# LoopAmp.net
KiCad netlist of a schematic drawn in EAGLE
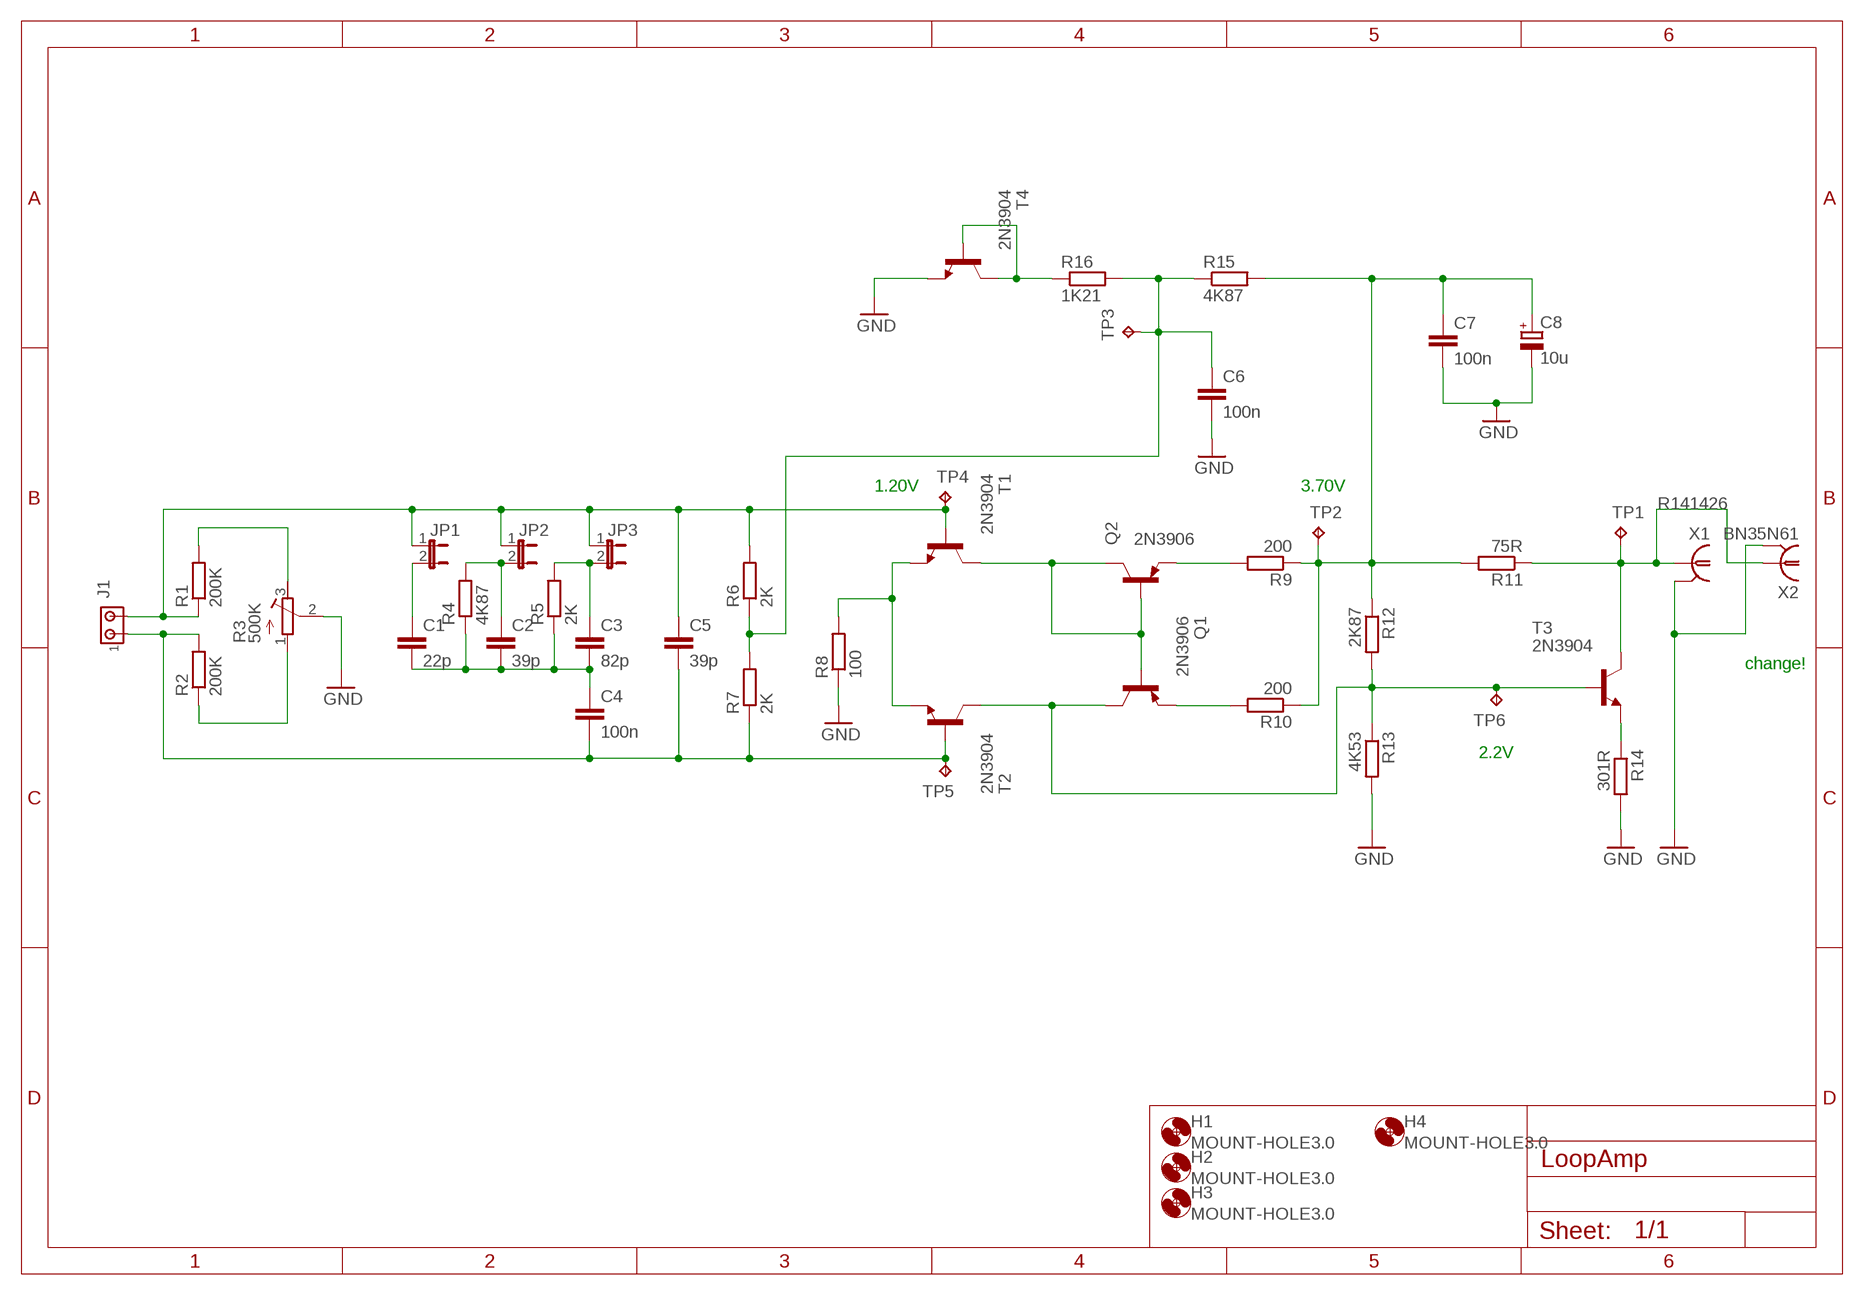
[diagram p0: schematic, sheet 1]

(export (version "E")
  (design (tool "Eeschema 10.0.6"))
  (components
    (comp (ref "C1")
      (value "22p")
      (footprint "eagle-import:C0805")
      (libsource (lib "eagle-import") (part "C-EUC0805"))
    )
    (comp (ref "C2")
      (value "39p")
      (footprint "eagle-import:C0805")
      (libsource (lib "eagle-import") (part "C-EUC0805"))
    )
    (comp (ref "C3")
      (value "82p")
      (footprint "eagle-import:C0805")
      (libsource (lib "eagle-import") (part "C-EUC0805"))
    )
    (comp (ref "C4")
      (value "100n")
      (footprint "eagle-import:C0805")
      (libsource (lib "eagle-import") (part "C-EUC0805"))
    )
    (comp (ref "C5")
      (value "39p")
      (footprint "eagle-import:C0805")
      (libsource (lib "eagle-import") (part "C-EUC0805"))
    )
    (comp (ref "C6")
      (value "100n")
      (footprint "eagle-import:C0805")
      (libsource (lib "eagle-import") (part "C-EUC0805"))
    )
    (comp (ref "C7")
      (value "100n")
      (footprint "eagle-import:C0805")
      (libsource (lib "eagle-import") (part "C-EUC0805"))
    )
    (comp (ref "C8")
      (value "10u")
      (footprint "eagle-import:PANASONIC_C")
      (libsource (lib "eagle-import") (part "CPOL-EUC"))
    )
    (comp (ref "H1")
      (value "MOUNT-HOLE3.0")
      (footprint "eagle-import:3,0")
      (libsource (lib "eagle-import") (part "MOUNT-HOLE3.0"))
    )
    (comp (ref "H2")
      (value "MOUNT-HOLE3.0")
      (footprint "eagle-import:3,0")
      (libsource (lib "eagle-import") (part "MOUNT-HOLE3.0"))
    )
    (comp (ref "H3")
      (value "MOUNT-HOLE3.0")
      (footprint "eagle-import:3,0")
      (libsource (lib "eagle-import") (part "MOUNT-HOLE3.0"))
    )
    (comp (ref "H4")
      (value "MOUNT-HOLE3.0")
      (footprint "eagle-import:3,0")
      (libsource (lib "eagle-import") (part "MOUNT-HOLE3.0"))
    )
    (comp (ref "J1")
      (value "MTA02-156")
      (footprint "eagle-import:1X2MTA")
      (libsource (lib "eagle-import") (part "MTA02-156"))
    )
    (comp (ref "JP1")
      (value "JP1E")
      (footprint "eagle-import:JP1")
      (libsource (lib "eagle-import") (part "JP1E"))
    )
    (comp (ref "JP2")
      (value "JP1E")
      (footprint "eagle-import:JP1")
      (libsource (lib "eagle-import") (part "JP1E"))
    )
    (comp (ref "JP3")
      (value "JP1E")
      (footprint "eagle-import:JP1")
      (libsource (lib "eagle-import") (part "JP1E"))
    )
    (comp (ref "Q1")
      (value "2N3906")
      (footprint "eagle-import:TO92")
      (libsource (lib "eagle-import") (part "2N3906"))
    )
    (comp (ref "Q2")
      (value "2N3906")
      (footprint "eagle-import:TO92")
      (libsource (lib "eagle-import") (part "2N3906"))
    )
    (comp (ref "R1")
      (value "200K")
      (footprint "eagle-import:R0805")
      (libsource (lib "eagle-import") (part "R-EU_R0805"))
    )
    (comp (ref "R2")
      (value "200K")
      (footprint "eagle-import:R0805")
      (libsource (lib "eagle-import") (part "R-EU_R0805"))
    )
    (comp (ref "R3")
      (value "500K")
      (footprint "eagle-import:RTRIM64W")
      (libsource (lib "eagle-import") (part "R-TRIMM64W"))
    )
    (comp (ref "R4")
      (value "4K87")
      (footprint "eagle-import:R0805")
      (libsource (lib "eagle-import") (part "R-EU_R0805"))
    )
    (comp (ref "R5")
      (value "2K")
      (footprint "eagle-import:R0805")
      (libsource (lib "eagle-import") (part "R-EU_R0805"))
    )
    (comp (ref "R6")
      (value "2K")
      (footprint "eagle-import:R0805")
      (libsource (lib "eagle-import") (part "R-EU_R0805"))
    )
    (comp (ref "R7")
      (value "2K")
      (footprint "eagle-import:R0805")
      (libsource (lib "eagle-import") (part "R-EU_R0805"))
    )
    (comp (ref "R8")
      (value "100")
      (footprint "eagle-import:R0805")
      (libsource (lib "eagle-import") (part "R-EU_R0805"))
    )
    (comp (ref "R9")
      (value "200")
      (footprint "eagle-import:R0805")
      (libsource (lib "eagle-import") (part "R-EU_R0805"))
    )
    (comp (ref "R10")
      (value "200")
      (footprint "eagle-import:R0805")
      (libsource (lib "eagle-import") (part "R-EU_R0805"))
    )
    (comp (ref "R11")
      (value "75R")
      (footprint "eagle-import:R0805")
      (libsource (lib "eagle-import") (part "R-EU_R0805"))
    )
    (comp (ref "R12")
      (value "2K87")
      (footprint "eagle-import:R0805")
      (libsource (lib "eagle-import") (part "R-EU_R0805"))
    )
    (comp (ref "R13")
      (value "4K53")
      (footprint "eagle-import:R0805")
      (libsource (lib "eagle-import") (part "R-EU_R0805"))
    )
    (comp (ref "R14")
      (value "301R")
      (footprint "eagle-import:R0805")
      (libsource (lib "eagle-import") (part "R-EU_R0805"))
    )
    (comp (ref "R15")
      (value "4K87")
      (footprint "eagle-import:R0805")
      (libsource (lib "eagle-import") (part "R-EU_R0805"))
    )
    (comp (ref "R16")
      (value "1K21")
      (footprint "eagle-import:R0805")
      (libsource (lib "eagle-import") (part "R-EU_R0805"))
    )
    (comp (ref "T1")
      (value "2N3904")
      (footprint "eagle-import:TO92")
      (libsource (lib "eagle-import") (part "2N3904"))
    )
    (comp (ref "T2")
      (value "2N3904")
      (footprint "eagle-import:TO92")
      (libsource (lib "eagle-import") (part "2N3904"))
    )
    (comp (ref "T3")
      (value "2N3904")
      (footprint "eagle-import:TO92")
      (libsource (lib "eagle-import") (part "2N3904"))
    )
    (comp (ref "T4")
      (value "2N3904")
      (footprint "eagle-import:TO92")
      (libsource (lib "eagle-import") (part "2N3904"))
    )
    (comp (ref "TP1")
      (value "4.18V>")
      (footprint "eagle-import:P1-13")
      (libsource (lib "eagle-import") (part "TPPAD1-13"))
    )
    (comp (ref "TP2")
      (value "4.18V>")
      (footprint "eagle-import:P1-13")
      (libsource (lib "eagle-import") (part "TPPAD1-13"))
    )
    (comp (ref "TP3")
      (value "4.18V>")
      (footprint "eagle-import:P1-13")
      (libsource (lib "eagle-import") (part "TPPAD1-13"))
    )
    (comp (ref "TP4")
      (value "4.18V>")
      (footprint "eagle-import:P1-13")
      (libsource (lib "eagle-import") (part "TPPAD1-13"))
    )
    (comp (ref "TP5")
      (value "4.18V>")
      (footprint "eagle-import:P1-13")
      (libsource (lib "eagle-import") (part "TPPAD1-13"))
    )
    (comp (ref "TP6")
      (value "4.18V>")
      (footprint "eagle-import:P1-13")
      (libsource (lib "eagle-import") (part "TPPAD1-13"))
    )
    (comp (ref "X1")
      (value "R141426")
      (footprint "eagle-import:R141426")
      (fields (field (name "MF") "FARNELL") (field (name "MPN") "R141426161"))
      (libsource (lib "eagle-import") (part "R141426"))
    )
    (comp (ref "X2")
      (value "BN35N61")
      (footprint "eagle-import:B35N61")
      (libsource (lib "eagle-import") (part "BN35N61"))
    )
  )
  (nets
    (net (code "1") (name "GND") (class "Default")
      (node (ref "C6") (pin "2") (pinfunction "2_2") (pintype "passive"))
      (node (ref "C7") (pin "2") (pinfunction "2_2") (pintype "passive"))
      (node (ref "C8") (pin "-") (pinfunction "-_-") (pintype "passive"))
      (node (ref "R13") (pin "2") (pinfunction "2_2") (pintype "passive"))
      (node (ref "R14") (pin "2") (pinfunction "2_2") (pintype "passive"))
      (node (ref "R3") (pin "2") (pinfunction "S_2") (pintype "passive"))
      (node (ref "R8") (pin "1") (pinfunction "1_1") (pintype "passive"))
      (node (ref "T4") (pin "3") (pinfunction "E_3") (pintype "passive"))
      (node (ref "X1") (pin "2") (pinfunction "2_2") (pintype "passive"))
      (node (ref "X1") (pin "3") (pinfunction "2_3") (pintype "passive"))
      (node (ref "X1") (pin "4") (pinfunction "2_4") (pintype "passive"))
      (node (ref "X1") (pin "5") (pinfunction "2_5") (pintype "passive"))
      (node (ref "X2") (pin "2") (pinfunction "2_2") (pintype "passive"))
      (node (ref "X2") (pin "3") (pinfunction "2_3") (pintype "passive"))
      (node (ref "X2") (pin "4") (pinfunction "2_4") (pintype "passive"))
      (node (ref "X2") (pin "5") (pinfunction "2_5") (pintype "passive"))
    )
    (net (code "2") (name "Net-(C1-Pad1)") (class "Default")
      (node (ref "C1") (pin "1") (pinfunction "1_1") (pintype "passive"))
      (node (ref "JP1") (pin "2") (pinfunction "2_2") (pintype "passive"))
    )
    (net (code "3") (name "Net-(C1-Pad2)") (class "Default")
      (node (ref "C1") (pin "2") (pinfunction "2_2") (pintype "passive"))
      (node (ref "C2") (pin "2") (pinfunction "2_2") (pintype "passive"))
      (node (ref "C3") (pin "2") (pinfunction "2_2") (pintype "passive"))
      (node (ref "C4") (pin "1") (pinfunction "1_1") (pintype "passive"))
      (node (ref "R4") (pin "1") (pinfunction "1_1") (pintype "passive"))
      (node (ref "R5") (pin "1") (pinfunction "1_1") (pintype "passive"))
    )
    (net (code "4") (name "Net-(C2-Pad1)") (class "Default")
      (node (ref "C2") (pin "1") (pinfunction "1_1") (pintype "passive"))
      (node (ref "JP2") (pin "2") (pinfunction "2_2") (pintype "passive"))
      (node (ref "R4") (pin "2") (pinfunction "2_2") (pintype "passive"))
    )
    (net (code "5") (name "Net-(C3-Pad1)") (class "Default")
      (node (ref "C3") (pin "1") (pinfunction "1_1") (pintype "passive"))
      (node (ref "JP3") (pin "2") (pinfunction "2_2") (pintype "passive"))
      (node (ref "R5") (pin "2") (pinfunction "2_2") (pintype "passive"))
    )
    (net (code "6") (name "Net-(C6-Pad1)") (class "Default")
      (node (ref "C6") (pin "1") (pinfunction "1_1") (pintype "passive"))
      (node (ref "R15") (pin "1") (pinfunction "1_1") (pintype "passive"))
      (node (ref "R16") (pin "2") (pinfunction "2_2") (pintype "passive"))
      (node (ref "R6") (pin "1") (pinfunction "1_1") (pintype "passive"))
      (node (ref "R7") (pin "2") (pinfunction "2_2") (pintype "passive"))
      (node (ref "TP3") (pin "TP") (pinfunction "TP_TP") (pintype "input"))
    )
    (net (code "7") (name "Net-(C7-Pad1)") (class "Default")
      (node (ref "C7") (pin "1") (pinfunction "1_1") (pintype "passive"))
      (node (ref "C8") (pin "+") (pinfunction "+_+") (pintype "passive"))
      (node (ref "R10") (pin "1") (pinfunction "1_1") (pintype "passive"))
      (node (ref "R11") (pin "2") (pinfunction "2_2") (pintype "passive"))
      (node (ref "R12") (pin "1") (pinfunction "1_1") (pintype "passive"))
      (node (ref "R15") (pin "2") (pinfunction "2_2") (pintype "passive"))
      (node (ref "R9") (pin "1") (pinfunction "1_1") (pintype "passive"))
      (node (ref "TP2") (pin "TP") (pinfunction "TP_TP") (pintype "input"))
    )
    (net (code "8") (name "Net-(Q1-B)") (class "Default")
      (node (ref "Q1") (pin "2") (pinfunction "B_2") (pintype "passive"))
      (node (ref "Q2") (pin "1") (pinfunction "C_1") (pintype "passive"))
      (node (ref "Q2") (pin "2") (pinfunction "B_2") (pintype "passive"))
      (node (ref "T1") (pin "1") (pinfunction "C_1") (pintype "passive"))
    )
    (net (code "9") (name "Net-(Q1-C)") (class "Default")
      (node (ref "Q1") (pin "1") (pinfunction "C_1") (pintype "passive"))
      (node (ref "R12") (pin "2") (pinfunction "2_2") (pintype "passive"))
      (node (ref "R13") (pin "1") (pinfunction "1_1") (pintype "passive"))
      (node (ref "T2") (pin "1") (pinfunction "C_1") (pintype "passive"))
      (node (ref "T3") (pin "2") (pinfunction "B_2") (pintype "passive"))
      (node (ref "TP6") (pin "TP") (pinfunction "TP_TP") (pintype "input"))
    )
    (net (code "10") (name "Net-(Q1-E)") (class "Default")
      (node (ref "Q1") (pin "3") (pinfunction "E_3") (pintype "passive"))
      (node (ref "R10") (pin "2") (pinfunction "2_2") (pintype "passive"))
    )
    (net (code "11") (name "Net-(Q2-E)") (class "Default")
      (node (ref "Q2") (pin "3") (pinfunction "E_3") (pintype "passive"))
      (node (ref "R9") (pin "2") (pinfunction "2_2") (pintype "passive"))
    )
    (net (code "12") (name "Net-(R3-A)") (class "Default")
      (node (ref "R2") (pin "1") (pinfunction "1_1") (pintype "passive"))
      (node (ref "R3") (pin "1") (pinfunction "A_1") (pintype "passive"))
    )
    (net (code "13") (name "Net-(R3-E)") (class "Default")
      (node (ref "R1") (pin "2") (pinfunction "2_2") (pintype "passive"))
      (node (ref "R3") (pin "3") (pinfunction "E_3") (pintype "passive"))
    )
    (net (code "14") (name "Net-(T1-B)") (class "Default")
      (node (ref "C5") (pin "1") (pinfunction "1_1") (pintype "passive"))
      (node (ref "J1") (pin "2") (pinfunction "2_2") (pintype "passive"))
      (node (ref "JP1") (pin "1") (pinfunction "1_1") (pintype "passive"))
      (node (ref "JP2") (pin "1") (pinfunction "1_1") (pintype "passive"))
      (node (ref "JP3") (pin "1") (pinfunction "1_1") (pintype "passive"))
      (node (ref "R1") (pin "1") (pinfunction "1_1") (pintype "passive"))
      (node (ref "R6") (pin "2") (pinfunction "2_2") (pintype "passive"))
      (node (ref "T1") (pin "2") (pinfunction "B_2") (pintype "passive"))
      (node (ref "TP4") (pin "TP") (pinfunction "TP_TP") (pintype "input"))
    )
    (net (code "15") (name "Net-(T1-E)") (class "Default")
      (node (ref "R8") (pin "2") (pinfunction "2_2") (pintype "passive"))
      (node (ref "T1") (pin "3") (pinfunction "E_3") (pintype "passive"))
      (node (ref "T2") (pin "3") (pinfunction "E_3") (pintype "passive"))
    )
    (net (code "16") (name "Net-(T2-B)") (class "Default")
      (node (ref "C4") (pin "2") (pinfunction "2_2") (pintype "passive"))
      (node (ref "C5") (pin "2") (pinfunction "2_2") (pintype "passive"))
      (node (ref "J1") (pin "1") (pinfunction "1_1") (pintype "passive"))
      (node (ref "R2") (pin "2") (pinfunction "2_2") (pintype "passive"))
      (node (ref "R7") (pin "1") (pinfunction "1_1") (pintype "passive"))
      (node (ref "T2") (pin "2") (pinfunction "B_2") (pintype "passive"))
      (node (ref "TP5") (pin "TP") (pinfunction "TP_TP") (pintype "input"))
    )
    (net (code "17") (name "Net-(T3-C)") (class "Default")
      (node (ref "R11") (pin "1") (pinfunction "1_1") (pintype "passive"))
      (node (ref "T3") (pin "1") (pinfunction "C_1") (pintype "passive"))
      (node (ref "TP1") (pin "TP") (pinfunction "TP_TP") (pintype "input"))
      (node (ref "X1") (pin "1") (pinfunction "1_1") (pintype "passive"))
      (node (ref "X2") (pin "1") (pinfunction "1_1") (pintype "passive"))
    )
    (net (code "18") (name "Net-(T3-E)") (class "Default")
      (node (ref "R14") (pin "1") (pinfunction "1_1") (pintype "passive"))
      (node (ref "T3") (pin "3") (pinfunction "E_3") (pintype "passive"))
    )
    (net (code "19") (name "Net-(T4-B)") (class "Default")
      (node (ref "R16") (pin "1") (pinfunction "1_1") (pintype "passive"))
      (node (ref "T4") (pin "1") (pinfunction "C_1") (pintype "passive"))
      (node (ref "T4") (pin "2") (pinfunction "B_2") (pintype "passive"))
    )
  )
)
